# MicroController.net
KiCad netlist of a schematic drawn in Altium Designer
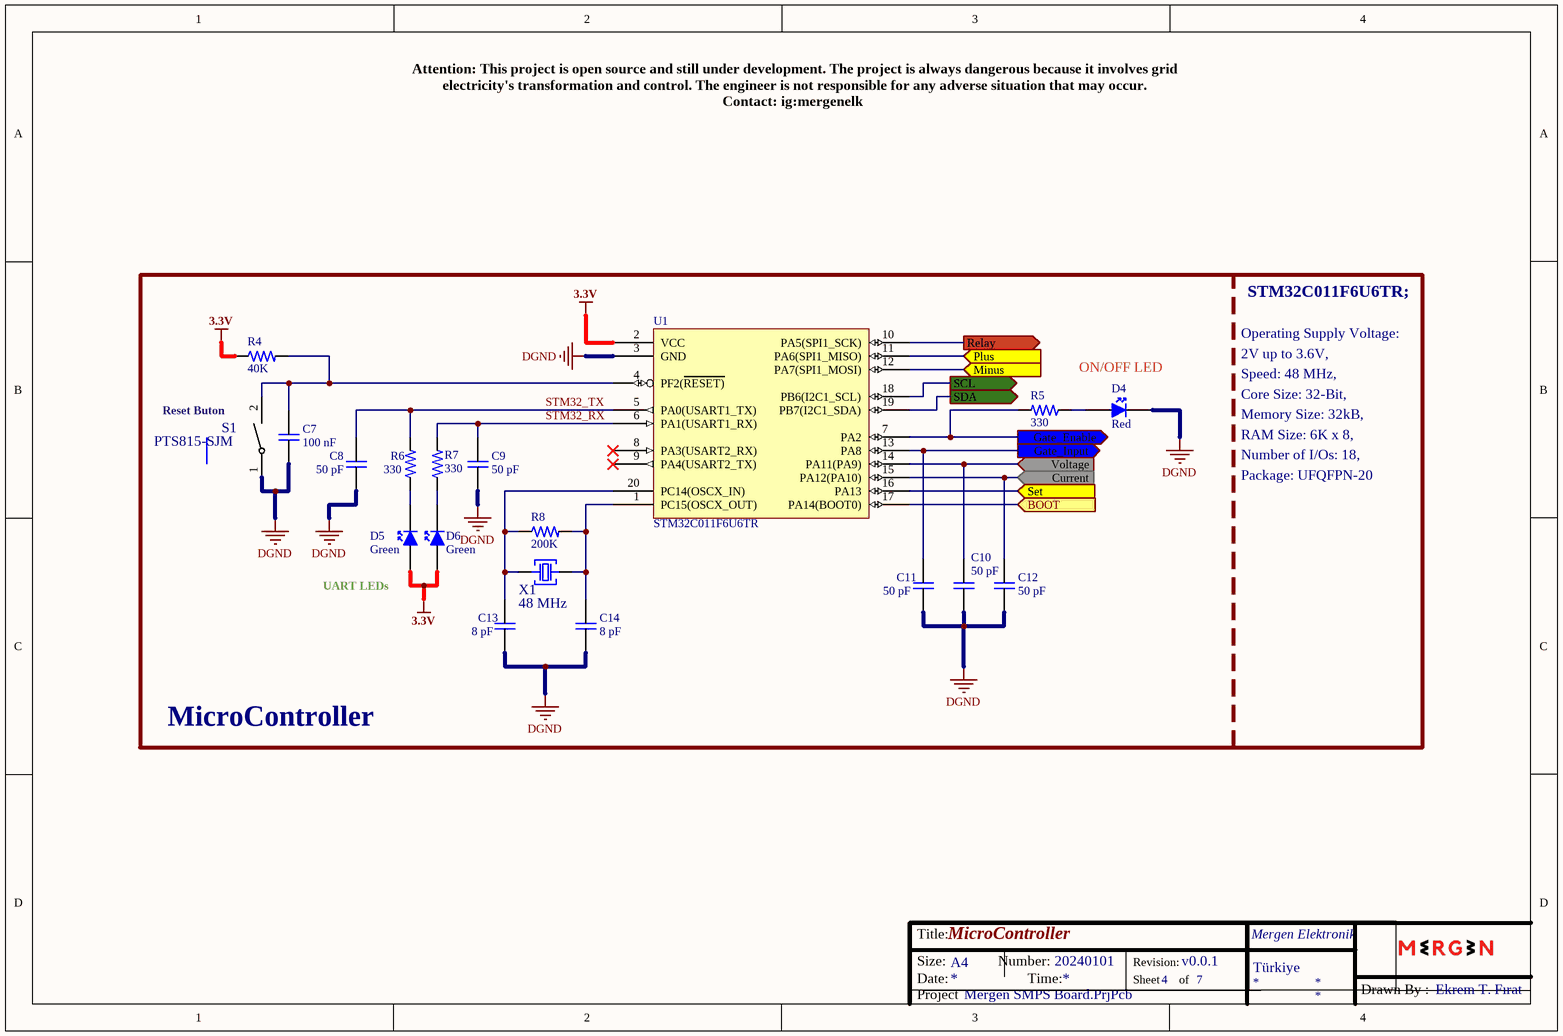
[diagram p0: MicroController.SchDoc]

(export (version "E")
  (design (tool "Eeschema 10.0.6"))
  (components
    (comp (ref "C7")
      (value "100 nF")
      (footprint "MergenElektronik_Capacitors_Ceramics_SMDs_0603_S_NS")
      (description "Mergen Elektronik - Capacitors - Ceramics - SMDs - 0603 - 100 nF - 16V")
      (fields (field (name "MANUFACTURER") "Samsung") (field (name "TOLERANCE") "±10%"))
      (libsource (lib "MergenElektronik_Capacitors_Ceramics_SMDs") (part "MergenElektronik_Capacitors_Ceramic_SMDs_100nF_16V"))
    )
    (comp (ref "C8")
      (value "50 pF")
      (footprint "MergenElektronik_Capacitors_Ceramics_SMDs_0402_S_NS")
      (description "Mergen Elektronik - Capacitors - Ceramics - SMDs - 0603 - 50 pF - 50V")
      (fields (field (name "MANUFACTURER") "YAGEO") (field (name "TOLERANCE") "±5%"))
      (libsource (lib "MergenElektronik_Capacitors_Ceramics_SMDs") (part "MergenElektronik_Capacitors_Ceramic_SMDs_50pF_50V"))
    )
    (comp (ref "C9")
      (value "50 pF")
      (footprint "MergenElektronik_Capacitors_Ceramics_SMDs_0402_S_NS")
      (description "Mergen Elektronik - Capacitors - Ceramics - SMDs - 0603 - 50 pF - 50V")
      (fields (field (name "MANUFACTURER") "YAGEO") (field (name "TOLERANCE") "±5%"))
      (libsource (lib "MergenElektronik_Capacitors_Ceramics_SMDs") (part "MergenElektronik_Capacitors_Ceramic_SMDs_50pF_50V"))
    )
    (comp (ref "C10")
      (value "50 pF")
      (footprint "MergenElektronik_Capacitors_Ceramics_SMDs_0402_S_NS")
      (description "Mergen Elektronik - Capacitors - Ceramics - SMDs - 0603 - 50 pF - 50V")
      (fields (field (name "MANUFACTURER") "YAGEO") (field (name "TOLERANCE") "±5%"))
      (libsource (lib "MergenElektronik_Capacitors_Ceramics_SMDs") (part "MergenElektronik_Capacitors_Ceramic_SMDs_50pF_50V"))
    )
    (comp (ref "C11")
      (value "50 pF")
      (footprint "MergenElektronik_Capacitors_Ceramics_SMDs_0402_S_NS")
      (description "Mergen Elektronik - Capacitors - Ceramics - SMDs - 0603 - 50 pF - 50V")
      (fields (field (name "MANUFACTURER") "YAGEO") (field (name "TOLERANCE") "±5%"))
      (libsource (lib "MergenElektronik_Capacitors_Ceramics_SMDs") (part "MergenElektronik_Capacitors_Ceramic_SMDs_50pF_50V"))
    )
    (comp (ref "C12")
      (value "50 pF")
      (footprint "MergenElektronik_Capacitors_Ceramics_SMDs_0402_S_NS")
      (description "Mergen Elektronik - Capacitors - Ceramics - SMDs - 0603 - 50 pF - 50V")
      (fields (field (name "MANUFACTURER") "YAGEO") (field (name "TOLERANCE") "±5%"))
      (libsource (lib "MergenElektronik_Capacitors_Ceramics_SMDs") (part "MergenElektronik_Capacitors_Ceramic_SMDs_50pF_50V"))
    )
    (comp (ref "C13")
      (value "8 pF")
      (footprint "MergenElektronik_Capacitors_Ceramics_SMDs_0603_S_NS")
      (description "Mergen Elektronik - Capacitors - Ceramics - SMDs - 0603 - 8 pF - 50V")
      (fields (field (name "MANUFACTURER") "YAGEO") (field (name "TOLERANCE") "±0.5pF"))
      (libsource (lib "MergenElektronik_Capacitors_Ceramics_SMDs") (part "MergenElektronik_Capacitors_Ceramic_SMDs_8pF_50V"))
    )
    (comp (ref "C14")
      (value "8 pF")
      (footprint "MergenElektronik_Capacitors_Ceramics_SMDs_0603_S_NS")
      (description "Mergen Elektronik - Capacitors - Ceramics - SMDs - 0603 - 8 pF - 50V")
      (fields (field (name "MANUFACTURER") "YAGEO") (field (name "TOLERANCE") "±0.5pF"))
      (libsource (lib "MergenElektronik_Capacitors_Ceramics_SMDs") (part "MergenElektronik_Capacitors_Ceramic_SMDs_8pF_50V"))
    )
    (comp (ref "D4")
      (value "Red")
      (footprint "MergenElektronik_Leds_SMDs_0603_S_NS")
      (description "Mergen Elektronik - Leds - SMDs - Red - 0603")
      (fields (field (name "MANUFACTURER") "Würth Elektronik"))
      (libsource (lib "MergenElektronik_Leds_SMDs") (part "MergenElektronik_LEDs_SMDs_Red_0603"))
    )
    (comp (ref "D5")
      (value "Green")
      (footprint "MergenElektronik_Leds_SMDs_0603_S_NS")
      (description "Mergen Elektronik - Leds - SMDs - Green - 0603")
      (fields (field (name "MANUFACTURER") "Würth Elektronik"))
      (libsource (lib "MergenElektronik_Leds_SMDs") (part "MergenElektronik_LEDs_SMDs_Green_0603"))
    )
    (comp (ref "D6")
      (value "Green")
      (footprint "MergenElektronik_Leds_SMDs_0603_S_NS")
      (description "Mergen Elektronik - Leds - SMDs - Green - 0603")
      (fields (field (name "MANUFACTURER") "Würth Elektronik"))
      (libsource (lib "MergenElektronik_Leds_SMDs") (part "MergenElektronik_LEDs_SMDs_Green_0603"))
    )
    (comp (ref "R4")
      (value "40K")
      (footprint "MergenElektronik_Resistors_ChipResistors_0603_S_NS")
      (description "Mergen Elektronik - Resistors - Chip Resistors - 0603 - 40K")
      (fields (field (name "MANUFACTURER") "YAGEO") (field (name "POWER") "1/10W"))
      (libsource (lib "MergenElektronik_Resistors_ChipResistors") (part "MergenElektronik_Resistors_ChipResistors_0603_40K"))
    )
    (comp (ref "R5")
      (value "330")
      (footprint "MergenElektronik_Resistors_ChipResistors_0603_S_NS")
      (description "Mergen Elektronik - Resistors - Chip Resistors - 0603 - 330R")
      (fields (field (name "MANUFACTURER") "Stackpole") (field (name "POWER") "1/10W"))
      (libsource (lib "MergenElektronik_Resistors_ChipResistors") (part "MergenElektronik_Resistors_ChipResistors_0603_330R"))
    )
    (comp (ref "R6")
      (value "330")
      (footprint "MergenElektronik_Resistors_ChipResistors_0603_S_NS")
      (description "Mergen Elektronik - Resistors - Chip Resistors - 0603 - 330R")
      (fields (field (name "MANUFACTURER") "Stackpole") (field (name "POWER") "1/10W"))
      (libsource (lib "MergenElektronik_Resistors_ChipResistors") (part "MergenElektronik_Resistors_ChipResistors_0603_330R"))
    )
    (comp (ref "R7")
      (value "330")
      (footprint "MergenElektronik_Resistors_ChipResistors_0603_S_NS")
      (description "Mergen Elektronik - Resistors - Chip Resistors - 0603 - 330R")
      (fields (field (name "MANUFACTURER") "Stackpole") (field (name "POWER") "1/10W"))
      (libsource (lib "MergenElektronik_Resistors_ChipResistors") (part "MergenElektronik_Resistors_ChipResistors_0603_330R"))
    )
    (comp (ref "R8")
      (value "200K")
      (footprint "MergenElektronik_Resistors_ChipResistors_0603_S_NS")
      (description "Mergen Elektronik - Resistors - Chip Resistors - 0603 - 200K")
      (fields (field (name "MANUFACTURER") "Stackpole") (field (name "POWER") "1/10W"))
      (libsource (lib "MergenElektronik_Resistors_ChipResistors") (part "MergenElektronik_Resistors_ChipResistors_0603_200K"))
    )
    (comp (ref "S1")
      (value "PTS815-SJM")
      (footprint "MergenElektronik_Switches_TactileSwitches_PTS815")
      (description "Mergen Elektronik - Switches - Tactile  Switches")
      (fields (field (name "MANUFACTURER") "C&K"))
      (libsource (lib "MergenElektronik_Switches_TactileSwitches") (part "MergenElektronik_Switches_TactileSwitches_PTS815-SJM"))
    )
    (comp (ref "U1")
      (value "STM32C011F6U6TR")
      (footprint "MergenElektronik_Microcontrollers_STMicroelectronics_UFQFPN-20")
      (description "Mergen Elektronik - Microcontrollers - STMicroelectronics - STM32C011F6U6TR")
      (fields (field (name "MANUFACTURER") "STMicroelectronics"))
      (libsource (lib "MergenElektronik_Microcontrollers_STMicroelectronics") (part "MergenElektronik_Microcontrollers_STMicroelectronics_STM32C011F6U6TR"))
    )
    (comp (ref "X1")
      (value "48 MHz")
      (footprint "MergenElektronik_Oscillators_Crystals_2-SMD")
      (description "Mergen Elektronik - Oscilators - Crystals - 2-SMD - 48 MHz")
      (fields (field (name "MANUFACTURER") "NDK America, Inc."))
      (libsource (lib "MergenElektronik_Oscillators_Crystals") (part "MergenElektronik_Oscillators_Crystals_2_SMD_48MHz"))
    )
  )
  (nets
    (net (code "1") (name "/BOOT") (class "Default")
      (node (ref "U1") (pin "17") (pinfunction "PA14(BOOT0)_17") (pintype "bidirectional"))
    )
    (net (code "2") (name "/Current") (class "Default")
      (node (ref "C12") (pin "1") (pinfunction "1_1") (pintype "passive"))
      (node (ref "U1") (pin "15") (pinfunction "PA12(PA10)_15") (pintype "bidirectional"))
    )
    (net (code "3") (name "/Gate_Enable") (class "Default")
      (node (ref "R5") (pin "2") (pinfunction "2_2") (pintype "passive"))
      (node (ref "U1") (pin "7") (pinfunction "PA2_7") (pintype "bidirectional"))
    )
    (net (code "4") (name "/Gate_Input") (class "Default")
      (node (ref "C11") (pin "1") (pinfunction "1_1") (pintype "passive"))
      (node (ref "U1") (pin "13") (pinfunction "PA8_13") (pintype "bidirectional"))
    )
    (net (code "5") (name "/Minus") (class "Default")
      (node (ref "U1") (pin "12") (pinfunction "PA7(SPI1_MOSI)_12") (pintype "bidirectional"))
    )
    (net (code "6") (name "/Plus") (class "Default")
      (node (ref "U1") (pin "11") (pinfunction "PA6(SPI1_MISO)_11") (pintype "bidirectional"))
    )
    (net (code "7") (name "/Relay") (class "Default")
      (node (ref "U1") (pin "10") (pinfunction "PA5(SPI1_SCK)_10") (pintype "bidirectional"))
    )
    (net (code "8") (name "/SCL") (class "Default")
      (node (ref "U1") (pin "18") (pinfunction "PB6(I2C1_SCL)_18") (pintype "bidirectional"))
    )
    (net (code "9") (name "/SDA") (class "Default")
      (node (ref "U1") (pin "19") (pinfunction "PB7(I2C1_SDA)_19") (pintype "bidirectional"))
    )
    (net (code "10") (name "/STM32_RX") (class "Default")
      (node (ref "C9") (pin "1") (pinfunction "1_1") (pintype "passive"))
      (node (ref "R7") (pin "2") (pinfunction "2_2") (pintype "passive"))
      (node (ref "U1") (pin "6") (pinfunction "PA1(USART1_RX)_6") (pintype "input"))
    )
    (net (code "11") (name "/STM32_TX") (class "Default")
      (node (ref "C8") (pin "1") (pinfunction "1_1") (pintype "passive"))
      (node (ref "R6") (pin "2") (pinfunction "2_2") (pintype "passive"))
      (node (ref "U1") (pin "5") (pinfunction "PA0(USART1_TX)_5") (pintype "output"))
    )
    (net (code "12") (name "/Set") (class "Default")
      (node (ref "U1") (pin "16") (pinfunction "PA13_16") (pintype "bidirectional"))
    )
    (net (code "13") (name "/Voltage") (class "Default")
      (node (ref "C10") (pin "1") (pinfunction "1_1") (pintype "passive"))
      (node (ref "U1") (pin "14") (pinfunction "PA11(PA9)_14") (pintype "bidirectional"))
    )
    (net (code "14") (name "3.3V") (class "Default")
      (node (ref "D5") (pin "1") (pinfunction "ANOT_1") (pintype "passive"))
      (node (ref "D6") (pin "1") (pinfunction "ANOT_1") (pintype "passive"))
      (node (ref "R4") (pin "1") (pinfunction "1_1") (pintype "passive"))
      (node (ref "U1") (pin "2") (pinfunction "VCC_2") (pintype "power_in"))
    )
    (net (code "15") (name "DGND") (class "Default")
      (node (ref "C10") (pin "2") (pinfunction "2_2") (pintype "passive"))
      (node (ref "C11") (pin "2") (pinfunction "2_2") (pintype "passive"))
      (node (ref "C12") (pin "2") (pinfunction "2_2") (pintype "passive"))
      (node (ref "C13") (pin "2") (pinfunction "2_2") (pintype "passive"))
      (node (ref "C14") (pin "2") (pinfunction "2_2") (pintype "passive"))
      (node (ref "C7") (pin "2") (pinfunction "2_2") (pintype "passive"))
      (node (ref "C8") (pin "2") (pinfunction "2_2") (pintype "passive"))
      (node (ref "C9") (pin "2") (pinfunction "2_2") (pintype "passive"))
      (node (ref "D4") (pin "2") (pinfunction "KATOT_2") (pintype "passive"))
      (node (ref "S1") (pin "1") (pinfunction "1_1") (pintype "passive"))
      (node (ref "U1") (pin "3") (pinfunction "GND_3") (pintype "power_in"))
    )
    (net (code "16") (name "Net-(D4-ANOT)") (class "Default")
      (node (ref "D4") (pin "1") (pinfunction "ANOT_1") (pintype "passive"))
      (node (ref "R5") (pin "1") (pinfunction "1_1") (pintype "passive"))
    )
    (net (code "17") (name "Net-(D5-KATOT)") (class "Default")
      (node (ref "D5") (pin "2") (pinfunction "KATOT_2") (pintype "passive"))
      (node (ref "R6") (pin "1") (pinfunction "1_1") (pintype "passive"))
    )
    (net (code "18") (name "Net-(D6-KATOT)") (class "Default")
      (node (ref "D6") (pin "2") (pinfunction "KATOT_2") (pintype "passive"))
      (node (ref "R7") (pin "1") (pinfunction "1_1") (pintype "passive"))
    )
    (net (code "19") (name "Net-(U1-PC14(OSCX_IN))") (class "Default")
      (node (ref "C13") (pin "1") (pinfunction "1_1") (pintype "passive"))
      (node (ref "R8") (pin "1") (pinfunction "1_1") (pintype "passive"))
      (node (ref "U1") (pin "20") (pinfunction "PC14(OSCX_IN)_20") (pintype "passive"))
      (node (ref "X1") (pin "1") (pinfunction "1_1") (pintype "passive"))
    )
    (net (code "20") (name "Net-(U1-PC15(OSCX_OUT))") (class "Default")
      (node (ref "C14") (pin "1") (pinfunction "1_1") (pintype "passive"))
      (node (ref "R8") (pin "2") (pinfunction "2_2") (pintype "passive"))
      (node (ref "U1") (pin "1") (pinfunction "PC15(OSCX_OUT)_1") (pintype "passive"))
      (node (ref "X1") (pin "2") (pinfunction "2_2") (pintype "passive"))
    )
    (net (code "21") (name "Net-(U1-PF2(RESET))") (class "Default")
      (node (ref "C7") (pin "1") (pinfunction "1_1") (pintype "passive"))
      (node (ref "R4") (pin "2") (pinfunction "2_2") (pintype "passive"))
      (node (ref "S1") (pin "2") (pinfunction "2_2") (pintype "passive"))
      (node (ref "U1") (pin "4") (pinfunction "PF2(RESET)_4") (pintype "bidirectional"))
    )
    (net (code "22") (name "unconnected-(U1-PA3(USART2_RX)-Pad8)") (class "Default")
      (node (ref "U1") (pin "8") (pinfunction "PA3(USART2_RX)_8") (pintype "input+no_connect"))
    )
    (net (code "23") (name "unconnected-(U1-PA4(USART2_TX)-Pad9)") (class "Default")
      (node (ref "U1") (pin "9") (pinfunction "PA4(USART2_TX)_9") (pintype "output+no_connect"))
    )
  )
)
